# 7SEG.net
KiCad netlist of a schematic drawn in Altium Designer
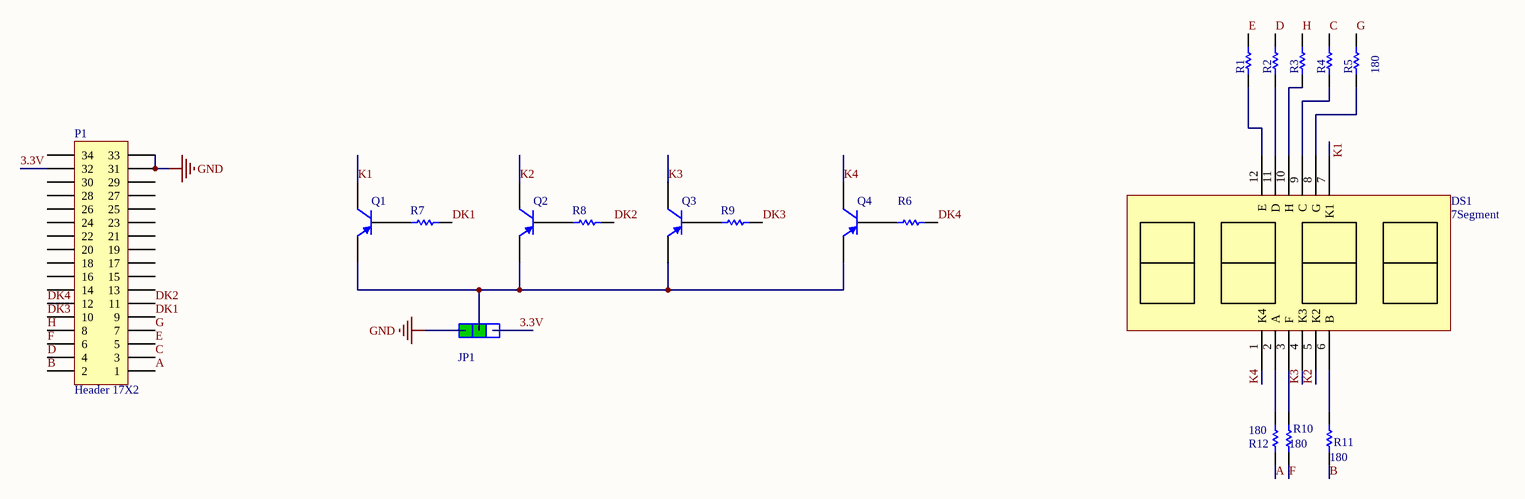
[diagram p0: 7SEG.SchDoc]

(export (version "E")
  (design (tool "Eeschema 10.0.6"))
  (components
    (comp (ref "DS1") (value "7Segment") (footprint "7Segment") (libsource (lib "Schlib1") (part "7Segment")))
    (comp (ref "JP1")
      (value "Jumper")
      (footprint "JT3")
      (description "Jumper Selector")
      (libsource (lib "Electrovolt Lib") (part "Jumper Selector"))
    )
    (comp (ref "P1")
      (value "Header 17X2")
      (footprint "HDR1X17")
      (description "Header, 17-Pin, Dual row")
      (fields (field (name "PUBLISHER") "Altium Limited"))
      (libsource (lib "Miscellaneous Connectors") (part "Header 17X2"))
    )
    (comp (ref "Q1")
      (value "BC857C")
      (footprint "SOT-23A_N")
      (description "PNP General Purpose Amplifier")
      (fields (field (name "PUBLISHER") "Altium Limited"))
      (libsource (lib "FSC Discrete BJT") (part "BC857C"))
    )
    (comp (ref "Q2")
      (value "BC857C")
      (footprint "SOT-23A_N")
      (description "PNP General Purpose Amplifier")
      (fields (field (name "PUBLISHER") "Altium Limited"))
      (libsource (lib "FSC Discrete BJT") (part "BC857C"))
    )
    (comp (ref "Q3")
      (value "BC857C")
      (footprint "SOT-23A_N")
      (description "PNP General Purpose Amplifier")
      (fields (field (name "PUBLISHER") "Altium Limited"))
      (libsource (lib "FSC Discrete BJT") (part "BC857C"))
    )
    (comp (ref "Q4")
      (value "BC857C")
      (footprint "SOT-23A_N")
      (description "PNP General Purpose Amplifier")
      (fields (field (name "PUBLISHER") "Altium Limited"))
      (libsource (lib "FSC Discrete BJT") (part "BC857C"))
    )
    (comp (ref "R1")
      (value "180")
      (footprint "1206")
      (description "Resistor")
      (fields (field (name "PUBLISHER") "Altium Limited"))
      (libsource (lib "Miscellaneous Devices") (part "Res1"))
    )
    (comp (ref "R2")
      (value "180")
      (footprint "1206")
      (description "Resistor")
      (fields (field (name "PUBLISHER") "Altium Limited"))
      (libsource (lib "Miscellaneous Devices") (part "Res1"))
    )
    (comp (ref "R3")
      (value "180")
      (footprint "1206")
      (description "Resistor")
      (fields (field (name "PUBLISHER") "Altium Limited"))
      (libsource (lib "Miscellaneous Devices") (part "Res1"))
    )
    (comp (ref "R4")
      (value "180")
      (footprint "1206")
      (description "Resistor")
      (fields (field (name "PUBLISHER") "Altium Limited"))
      (libsource (lib "Miscellaneous Devices") (part "Res1"))
    )
    (comp (ref "R5")
      (value "180")
      (footprint "1206")
      (description "Resistor")
      (fields (field (name "PUBLISHER") "Altium Limited"))
      (libsource (lib "Miscellaneous Devices") (part "Res1"))
    )
    (comp (ref "R6")
      (value "10K")
      (footprint "1206")
      (description "Resistor")
      (fields (field (name "PUBLISHER") "Altium Limited"))
      (libsource (lib "Miscellaneous Devices") (part "Res1"))
    )
    (comp (ref "R7")
      (value "10K")
      (footprint "1206")
      (description "Resistor")
      (fields (field (name "PUBLISHER") "Altium Limited"))
      (libsource (lib "Miscellaneous Devices") (part "Res1"))
    )
    (comp (ref "R8")
      (value "10K")
      (footprint "1206")
      (description "Resistor")
      (fields (field (name "PUBLISHER") "Altium Limited"))
      (libsource (lib "Miscellaneous Devices") (part "Res1"))
    )
    (comp (ref "R9")
      (value "10K")
      (footprint "1206")
      (description "Resistor")
      (fields (field (name "PUBLISHER") "Altium Limited"))
      (libsource (lib "Miscellaneous Devices") (part "Res1"))
    )
    (comp (ref "R10")
      (value "180")
      (footprint "1206")
      (description "Resistor")
      (fields (field (name "PUBLISHER") "Altium Limited"))
      (libsource (lib "Miscellaneous Devices") (part "Res1"))
    )
    (comp (ref "R11")
      (value "180")
      (footprint "1206")
      (description "Resistor")
      (fields (field (name "PUBLISHER") "Altium Limited"))
      (libsource (lib "Miscellaneous Devices") (part "Res1"))
    )
    (comp (ref "R12")
      (value "180")
      (footprint "1206")
      (description "Resistor")
      (fields (field (name "PUBLISHER") "Altium Limited"))
      (libsource (lib "Miscellaneous Devices") (part "Res1"))
    )
  )
  (nets
    (net (code "1") (name "/3.3V") (class "Default")
      (node (ref "JP1") (pin "3") (pinfunction "3_3") (pintype "passive"))
      (node (ref "P1") (pin "32") (pinfunction "32_32") (pintype "passive"))
    )
    (net (code "2") (name "/A") (class "Default")
      (node (ref "P1") (pin "1") (pinfunction "1_1") (pintype "passive"))
      (node (ref "R12") (pin "2") (pinfunction "2_2") (pintype "passive"))
    )
    (net (code "3") (name "/B") (class "Default")
      (node (ref "P1") (pin "2") (pinfunction "2_2") (pintype "passive"))
      (node (ref "R11") (pin "2") (pinfunction "2_2") (pintype "passive"))
    )
    (net (code "4") (name "/C") (class "Default")
      (node (ref "P1") (pin "3") (pinfunction "3_3") (pintype "passive"))
      (node (ref "R4") (pin "1") (pinfunction "1_1") (pintype "passive"))
    )
    (net (code "5") (name "/D") (class "Default")
      (node (ref "P1") (pin "4") (pinfunction "4_4") (pintype "passive"))
      (node (ref "R2") (pin "1") (pinfunction "1_1") (pintype "passive"))
    )
    (net (code "6") (name "/DK1") (class "Default")
      (node (ref "P1") (pin "9") (pinfunction "9_9") (pintype "passive"))
      (node (ref "R7") (pin "2") (pinfunction "2_2") (pintype "passive"))
    )
    (net (code "7") (name "/DK2") (class "Default")
      (node (ref "P1") (pin "11") (pinfunction "11_11") (pintype "passive"))
      (node (ref "R8") (pin "2") (pinfunction "2_2") (pintype "passive"))
    )
    (net (code "8") (name "/DK3") (class "Default")
      (node (ref "P1") (pin "10") (pinfunction "10_10") (pintype "passive"))
      (node (ref "R9") (pin "2") (pinfunction "2_2") (pintype "passive"))
    )
    (net (code "9") (name "/DK4") (class "Default")
      (node (ref "P1") (pin "12") (pinfunction "12_12") (pintype "passive"))
      (node (ref "R6") (pin "2") (pinfunction "2_2") (pintype "passive"))
    )
    (net (code "10") (name "/E") (class "Default")
      (node (ref "P1") (pin "5") (pinfunction "5_5") (pintype "passive"))
      (node (ref "R1") (pin "1") (pinfunction "1_1") (pintype "passive"))
    )
    (net (code "11") (name "/F") (class "Default")
      (node (ref "P1") (pin "6") (pinfunction "6_6") (pintype "passive"))
      (node (ref "R10") (pin "2") (pinfunction "2_2") (pintype "passive"))
    )
    (net (code "12") (name "/G") (class "Default")
      (node (ref "P1") (pin "7") (pinfunction "7_7") (pintype "passive"))
      (node (ref "R5") (pin "1") (pinfunction "1_1") (pintype "passive"))
    )
    (net (code "13") (name "/H") (class "Default")
      (node (ref "P1") (pin "8") (pinfunction "8_8") (pintype "passive"))
      (node (ref "R3") (pin "1") (pinfunction "1_1") (pintype "passive"))
    )
    (net (code "14") (name "/K1") (class "Default")
      (node (ref "DS1") (pin "7") (pinfunction "K1_7") (pintype "passive"))
      (node (ref "Q1") (pin "3") (pinfunction "C_3") (pintype "passive"))
    )
    (net (code "15") (name "/K2") (class "Default")
      (node (ref "DS1") (pin "5") (pinfunction "K2_5") (pintype "passive"))
      (node (ref "Q2") (pin "3") (pinfunction "C_3") (pintype "passive"))
    )
    (net (code "16") (name "/K3") (class "Default")
      (node (ref "DS1") (pin "4") (pinfunction "K3_4") (pintype "passive"))
      (node (ref "Q3") (pin "3") (pinfunction "C_3") (pintype "passive"))
    )
    (net (code "17") (name "/K4") (class "Default")
      (node (ref "DS1") (pin "1") (pinfunction "K4_1") (pintype "passive"))
      (node (ref "Q4") (pin "3") (pinfunction "C_3") (pintype "passive"))
    )
    (net (code "18") (name "GND") (class "Default")
      (node (ref "JP1") (pin "1") (pinfunction "1_1") (pintype "passive"))
      (node (ref "P1") (pin "31") (pinfunction "31_31") (pintype "passive"))
      (node (ref "P1") (pin "33") (pinfunction "33_33") (pintype "passive"))
    )
    (net (code "19") (name "Net-(DS1-A)") (class "Default")
      (node (ref "DS1") (pin "2") (pinfunction "A_2") (pintype "passive"))
      (node (ref "R12") (pin "1") (pinfunction "1_1") (pintype "passive"))
    )
    (net (code "20") (name "Net-(DS1-B)") (class "Default")
      (node (ref "DS1") (pin "6") (pinfunction "B_6") (pintype "passive"))
      (node (ref "R11") (pin "1") (pinfunction "1_1") (pintype "passive"))
    )
    (net (code "21") (name "Net-(DS1-C)") (class "Default")
      (node (ref "DS1") (pin "9") (pinfunction "C_9") (pintype "passive"))
      (node (ref "R4") (pin "2") (pinfunction "2_2") (pintype "passive"))
    )
    (net (code "22") (name "Net-(DS1-D)") (class "Default")
      (node (ref "DS1") (pin "11") (pinfunction "D_11") (pintype "passive"))
      (node (ref "R2") (pin "2") (pinfunction "2_2") (pintype "passive"))
    )
    (net (code "23") (name "Net-(DS1-E)") (class "Default")
      (node (ref "DS1") (pin "12") (pinfunction "E_12") (pintype "passive"))
      (node (ref "R1") (pin "2") (pinfunction "2_2") (pintype "passive"))
    )
    (net (code "24") (name "Net-(DS1-F)") (class "Default")
      (node (ref "DS1") (pin "3") (pinfunction "F_3") (pintype "passive"))
      (node (ref "R10") (pin "1") (pinfunction "1_1") (pintype "passive"))
    )
    (net (code "25") (name "Net-(DS1-G)") (class "Default")
      (node (ref "DS1") (pin "8") (pinfunction "G_8") (pintype "passive"))
      (node (ref "R5") (pin "2") (pinfunction "2_2") (pintype "passive"))
    )
    (net (code "26") (name "Net-(DS1-H)") (class "Default")
      (node (ref "DS1") (pin "10") (pinfunction "H_10") (pintype "passive"))
      (node (ref "R3") (pin "2") (pinfunction "2_2") (pintype "passive"))
    )
    (net (code "27") (name "Net-(Q1-B)") (class "Default")
      (node (ref "Q1") (pin "1") (pinfunction "B_1") (pintype "passive"))
      (node (ref "R7") (pin "1") (pinfunction "1_1") (pintype "passive"))
    )
    (net (code "28") (name "Net-(Q1-E)") (class "Default")
      (node (ref "JP1") (pin "2") (pinfunction "2_2") (pintype "passive"))
      (node (ref "Q1") (pin "2") (pinfunction "E_2") (pintype "passive"))
      (node (ref "Q2") (pin "2") (pinfunction "E_2") (pintype "passive"))
      (node (ref "Q3") (pin "2") (pinfunction "E_2") (pintype "passive"))
      (node (ref "Q4") (pin "2") (pinfunction "E_2") (pintype "passive"))
    )
    (net (code "29") (name "Net-(Q2-B)") (class "Default")
      (node (ref "Q2") (pin "1") (pinfunction "B_1") (pintype "passive"))
      (node (ref "R8") (pin "1") (pinfunction "1_1") (pintype "passive"))
    )
    (net (code "30") (name "Net-(Q3-B)") (class "Default")
      (node (ref "Q3") (pin "1") (pinfunction "B_1") (pintype "passive"))
      (node (ref "R9") (pin "1") (pinfunction "1_1") (pintype "passive"))
    )
    (net (code "31") (name "Net-(Q4-B)") (class "Default")
      (node (ref "Q4") (pin "1") (pinfunction "B_1") (pintype "passive"))
      (node (ref "R6") (pin "1") (pinfunction "1_1") (pintype "passive"))
    )
    (net (code "32") (name "unconnected-(P1-Pad13)") (class "Default")
      (node (ref "P1") (pin "13") (pinfunction "13_13") (pintype "passive"))
    )
    (net (code "33") (name "unconnected-(P1-Pad14)") (class "Default")
      (node (ref "P1") (pin "14") (pinfunction "14_14") (pintype "passive"))
    )
    (net (code "34") (name "unconnected-(P1-Pad15)") (class "Default")
      (node (ref "P1") (pin "15") (pinfunction "15_15") (pintype "passive"))
    )
    (net (code "35") (name "unconnected-(P1-Pad16)") (class "Default")
      (node (ref "P1") (pin "16") (pinfunction "16_16") (pintype "passive"))
    )
    (net (code "36") (name "unconnected-(P1-Pad17)") (class "Default")
      (node (ref "P1") (pin "17") (pinfunction "17_17") (pintype "passive"))
    )
    (net (code "37") (name "unconnected-(P1-Pad18)") (class "Default")
      (node (ref "P1") (pin "18") (pinfunction "18_18") (pintype "passive"))
    )
    (net (code "38") (name "unconnected-(P1-Pad19)") (class "Default")
      (node (ref "P1") (pin "19") (pinfunction "19_19") (pintype "passive"))
    )
    (net (code "39") (name "unconnected-(P1-Pad20)") (class "Default")
      (node (ref "P1") (pin "20") (pinfunction "20_20") (pintype "passive"))
    )
    (net (code "40") (name "unconnected-(P1-Pad21)") (class "Default")
      (node (ref "P1") (pin "21") (pinfunction "21_21") (pintype "passive"))
    )
    (net (code "41") (name "unconnected-(P1-Pad22)") (class "Default")
      (node (ref "P1") (pin "22") (pinfunction "22_22") (pintype "passive"))
    )
    (net (code "42") (name "unconnected-(P1-Pad23)") (class "Default")
      (node (ref "P1") (pin "23") (pinfunction "23_23") (pintype "passive"))
    )
    (net (code "43") (name "unconnected-(P1-Pad24)") (class "Default")
      (node (ref "P1") (pin "24") (pinfunction "24_24") (pintype "passive"))
    )
    (net (code "44") (name "unconnected-(P1-Pad25)") (class "Default")
      (node (ref "P1") (pin "25") (pinfunction "25_25") (pintype "passive"))
    )
    (net (code "45") (name "unconnected-(P1-Pad26)") (class "Default")
      (node (ref "P1") (pin "26") (pinfunction "26_26") (pintype "passive"))
    )
    (net (code "46") (name "unconnected-(P1-Pad27)") (class "Default")
      (node (ref "P1") (pin "27") (pinfunction "27_27") (pintype "passive"))
    )
    (net (code "47") (name "unconnected-(P1-Pad28)") (class "Default")
      (node (ref "P1") (pin "28") (pinfunction "28_28") (pintype "passive"))
    )
    (net (code "48") (name "unconnected-(P1-Pad29)") (class "Default")
      (node (ref "P1") (pin "29") (pinfunction "29_29") (pintype "passive"))
    )
    (net (code "49") (name "unconnected-(P1-Pad30)") (class "Default")
      (node (ref "P1") (pin "30") (pinfunction "30_30") (pintype "passive"))
    )
    (net (code "50") (name "unconnected-(P1-Pad34)") (class "Default")
      (node (ref "P1") (pin "34") (pinfunction "34_34") (pintype "passive"))
    )
  )
)
